# TASHIMASU_MAINBOARD_2020-07-29_17-58-20.net
KiCad netlist of a schematic drawn in EasyEDA
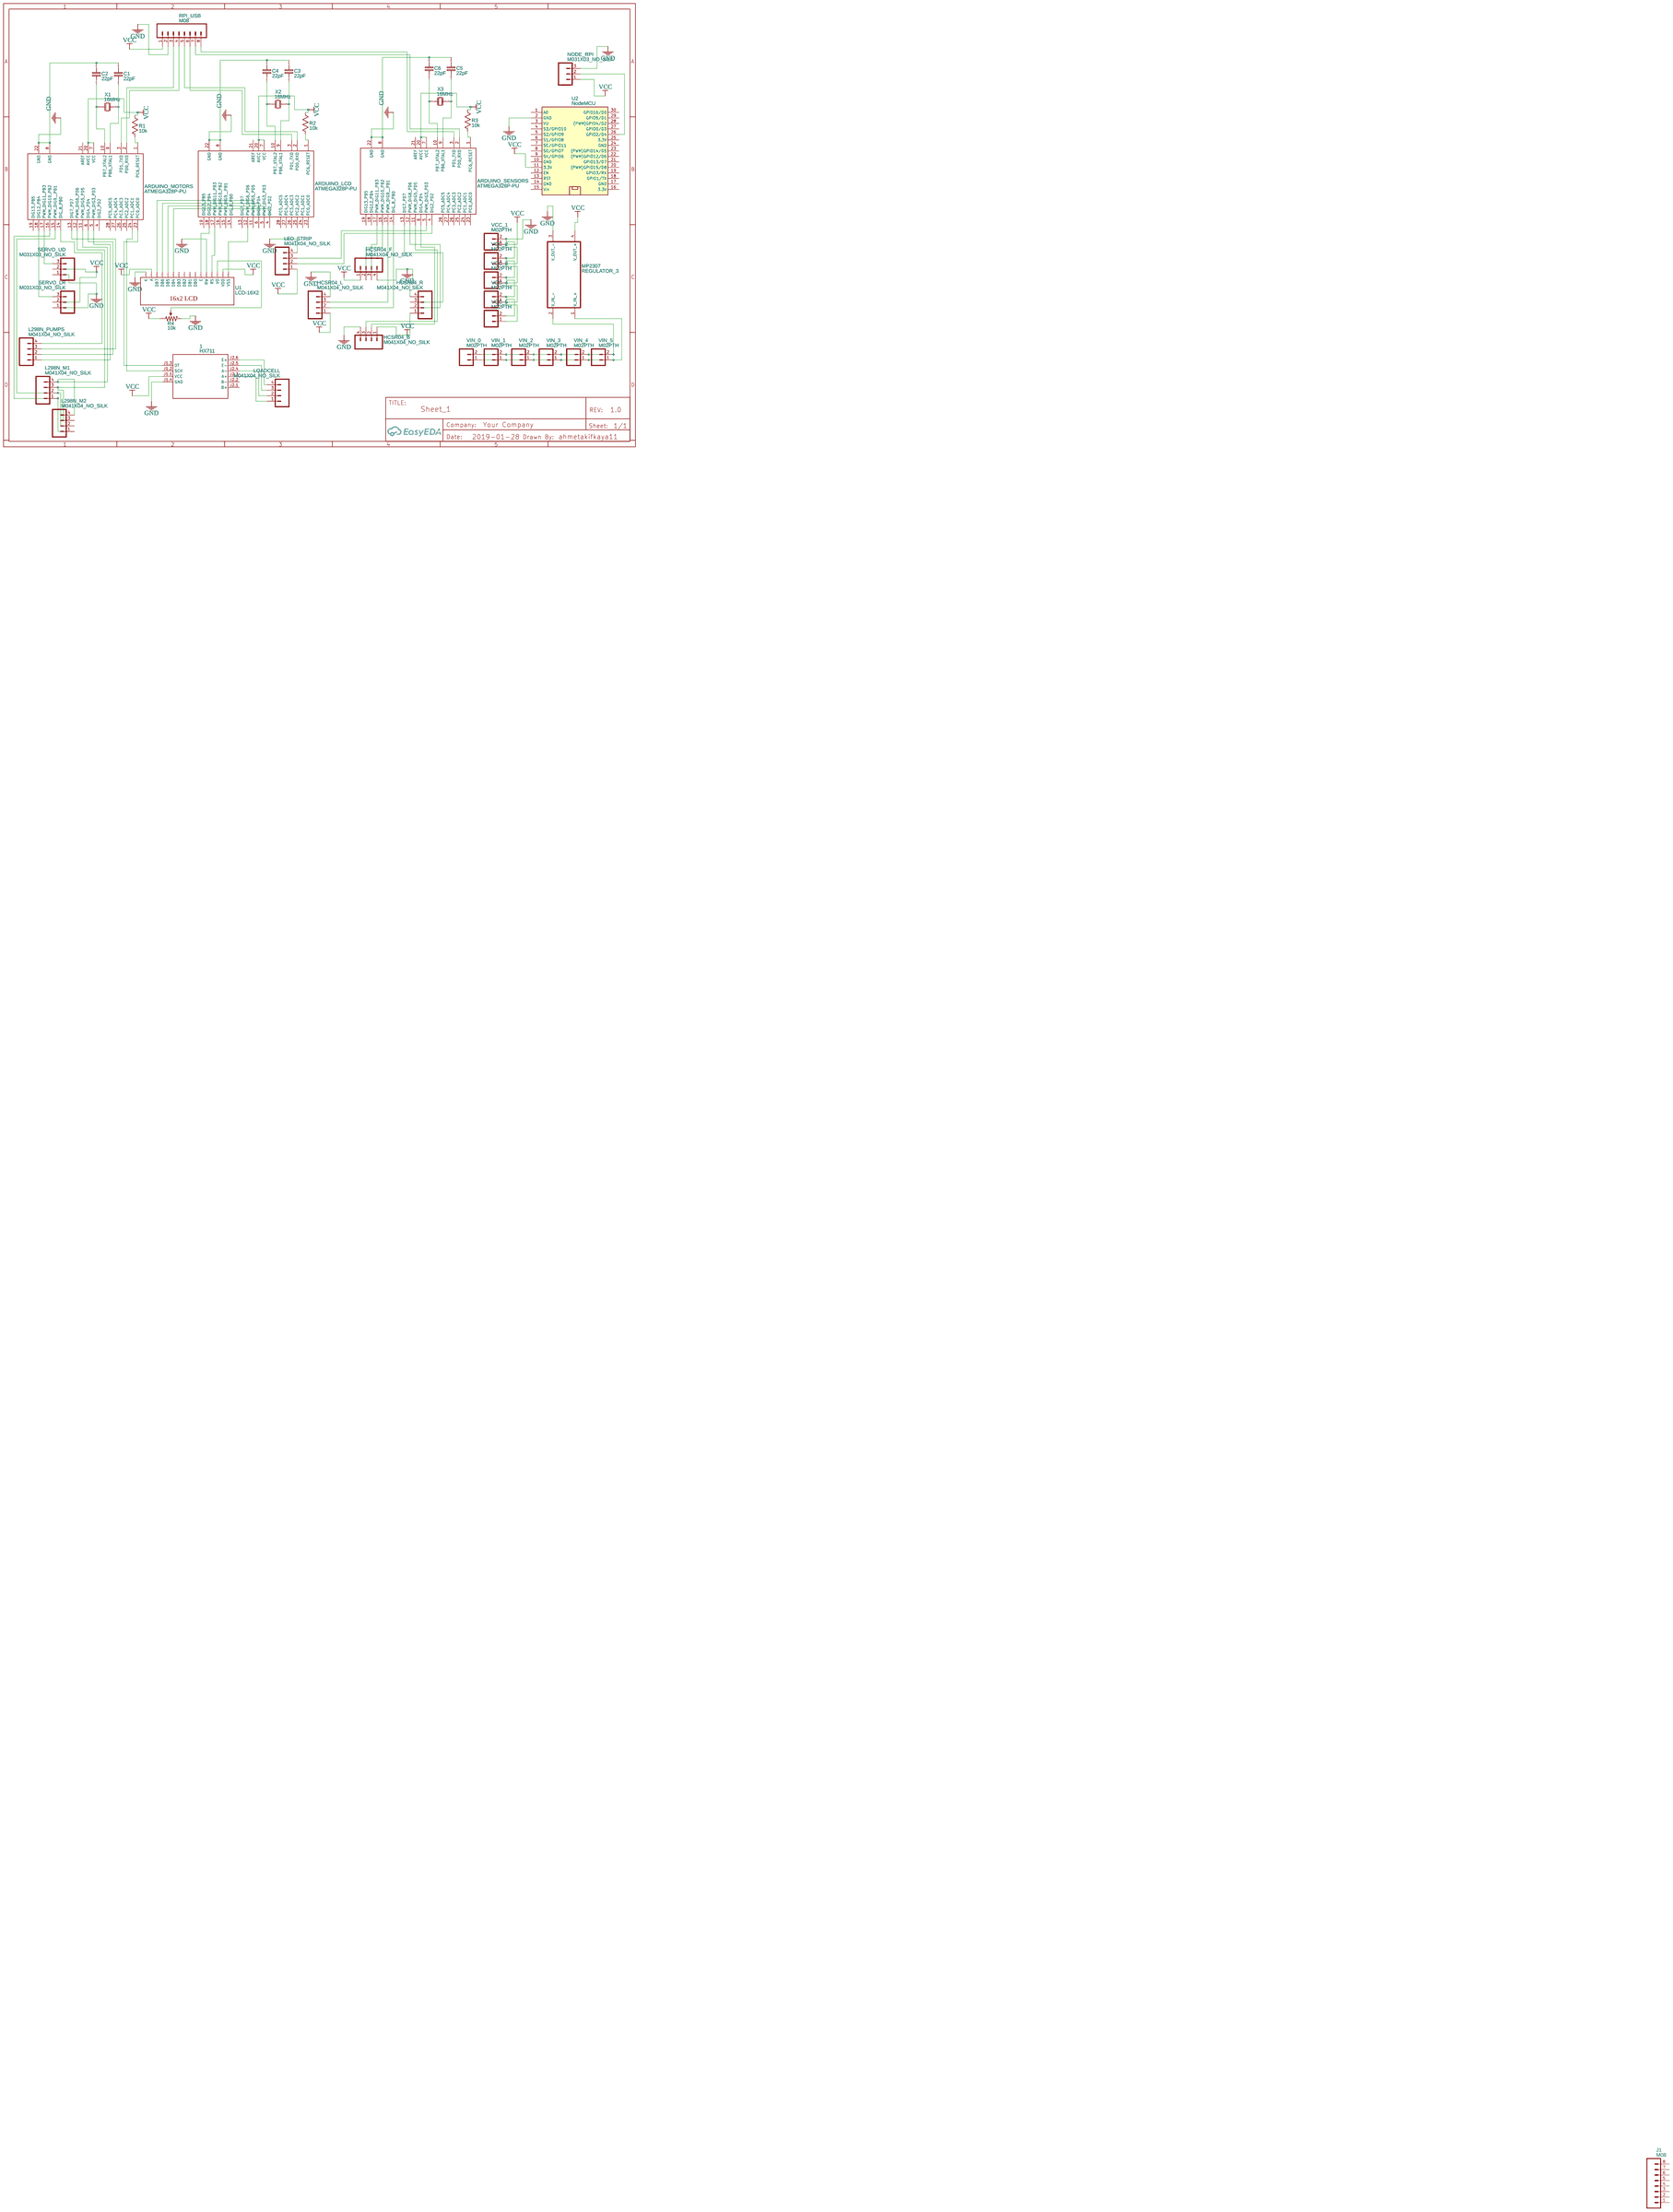
[diagram p0: schematic sheet]

(export (version "E")
  (design (tool "Eeschema 10.0.6"))
  (components
    (comp (ref "1")
      (value "HX711")
      (fields (field (name "BOM_Manufacturer Part") "?"))
      (libsource (lib "") (part "Unknown_350_680"))
    )
    (comp (ref "ARDUINO_LCD")
      (value "ATMEGA328P-PU")
      (fields (field (name "BOM_Supplier Part") "C33901"))
      (libsource (lib "") (part "Unknown_450_330"))
    )
    (comp (ref "ARDUINO_MOTORS")
      (value "ATMEGA328P-PU")
      (fields (field (name "BOM_Supplier Part") "C33901"))
      (libsource (lib "") (part "Unknown_140_335"))
    )
    (comp (ref "ARDUINO_SENSORS")
      (value "ATMEGA328P-PU")
      (fields (field (name "BOM_Supplier Part") "C33901"))
      (libsource (lib "") (part "Unknown_745_325"))
    )
    (comp (ref "C1")
      (value "22pF")
      (fields (field (name "BOM_Manufacturer Part") "?"))
      (libsource (lib "") (part "Cap_RAD-0.1_EU_1"))
    )
    (comp (ref "C2")
      (value "22pF")
      (fields (field (name "BOM_Manufacturer Part") "?"))
      (libsource (lib "") (part "Cap_RAD-0.1_EU_1"))
    )
    (comp (ref "C3")
      (value "22pF")
      (fields (field (name "BOM_Manufacturer Part") "?"))
      (libsource (lib "") (part "Cap_RAD-0.1_EU"))
    )
    (comp (ref "C4")
      (value "22pF")
      (fields (field (name "BOM_Manufacturer Part") "?"))
      (libsource (lib "") (part "Cap_RAD-0.1_EU_2"))
    )
    (comp (ref "C5")
      (value "22pF")
      (fields (field (name "BOM_Manufacturer Part") "?"))
      (libsource (lib "") (part "Cap_RAD-0.1_EU"))
    )
    (comp (ref "C6")
      (value "22pF")
      (fields (field (name "BOM_Manufacturer Part") "?"))
      (libsource (lib "") (part "Cap_RAD-0.1_EU"))
    )
    (comp (ref "HCSR04_B")
      (value "M041X04_NO_SILK")
      (fields (field (name "BOM_Manufacturer Part") "?"))
      (libsource (lib "") (part "Unknown_660_610"))
    )
    (comp (ref "HCSR04_F")
      (value "M041X04_NO_SILK")
      (fields (field (name "BOM_Manufacturer Part") "?"))
      (libsource (lib "") (part "Unknown_650_485"))
    )
    (comp (ref "HCSR04_L")
      (value "M041X04_NO_SILK")
      (fields (field (name "BOM_Manufacturer Part") "?"))
      (libsource (lib "") (part "Unknown_565_555"))
    )
    (comp (ref "HCSR04_R")
      (value "M041X04_NO_SILK")
      (fields (field (name "BOM_Manufacturer Part") "?"))
      (libsource (lib "") (part "Unknown_750_555"))
    )
    (comp (ref "J1")
      (value "M08")
      (fields (field (name "BOM_Manufacturer Part") "?"))
      (libsource (lib "") (part "Unknown_3000_4000"))
    )
    (comp (ref "L298N_M1")
      (value "M041X04_NO_SILK")
      (fields (field (name "BOM_Manufacturer Part") "?"))
      (libsource (lib "") (part "Unknown_70_710"))
    )
    (comp (ref "L298N_M2")
      (value "M041X04_NO_SILK")
      (fields (field (name "BOM_Manufacturer Part") "?"))
      (libsource (lib "") (part "Unknown_100_770"))
    )
    (comp (ref "L298N_PUMPS")
      (value "M041X04_NO_SILK")
      (fields (field (name "BOM_Manufacturer Part") "?"))
      (libsource (lib "") (part "Unknown_40_640"))
    )
    (comp (ref "LED_STRIP")
      (value "M041X04_NO_SILK")
      (fields (field (name "BOM_Manufacturer Part") "?"))
      (libsource (lib "") (part "Unknown_505_475"))
    )
    (comp (ref "LOADCELL")
      (value "M041X04_NO_SILK")
      (fields (field (name "BOM_Manufacturer Part") "?"))
      (libsource (lib "") (part "Unknown_490_715"))
    )
    (comp (ref "NODE_RPI")
      (value "M031X03_NO_SILK")
      (fields (field (name "BOM_Manufacturer Part") "?"))
      (libsource (lib "") (part "Unknown_1010_130"))
    )
    (comp (ref "R1")
      (value "10k")
      (fields (field (name "BOM_Manufacturer Part") "?"))
      (libsource (lib "") (part "Res_AXIAL-0.3(1/8W)_US"))
    )
    (comp (ref "R2")
      (value "10k")
      (fields (field (name "BOM_Manufacturer Part") "?"))
      (libsource (lib "") (part "Res_AXIAL-0.3(1/8W)_US"))
    )
    (comp (ref "R3")
      (value "10k")
      (fields (field (name "BOM_Manufacturer Part") "?"))
      (libsource (lib "") (part "Res_AXIAL-0.3(1/8W)_US"))
    )
    (comp (ref "R4")
      (value "10k")
      (fields
        (field (name "BOM_Manufacturer Part") "3386P-1-101LF")
        (field (name "BOM_Supplier Part") "C125022")
      )
      (libsource (lib "") (part "3386P-1-101LF_US"))
    )
    (comp (ref "REGULATOR_3")
      (value "MP2307")
      (fields (field (name "BOM_Manufacturer Part") "?"))
      (libsource (lib "") (part "Unknown_1010_565"))
    )
    (comp (ref "RPI_USB")
      (value "M08")
      (fields (field (name "BOM_Manufacturer Part") "?"))
      (libsource (lib "") (part "Unknown_280_60"))
    )
    (comp (ref "SERVO_LR")
      (value "M031X03_NO_SILK")
      (fields (field (name "BOM_Manufacturer Part") "?"))
      (libsource (lib "") (part "Unknown_110_545"))
    )
    (comp (ref "SERVO_UD")
      (value "M031X03_NO_SILK")
      (fields (field (name "BOM_Manufacturer Part") "?"))
      (libsource (lib "") (part "Unknown_110_485"))
    )
    (comp (ref "U1")
      (value "LCD-16X2")
      (fields (field (name "BOM_Manufacturer Part") "?"))
      (libsource (lib "") (part "Unknown_325_520"))
    )
    (comp (ref "U2")
      (value "NodeMCU")
      (fields (field (name "BOM_Manufacturer Part") "NodeMcu V3 LoLin"))
      (libsource (lib "") (part "Unknown_950_200"))
    )
    (comp (ref "VCC_1")
      (value "M02PTH")
      (fields (field (name "BOM_Manufacturer Part") "?"))
      (libsource (lib "") (part "Unknown_875_440"))
    )
    (comp (ref "VCC_2")
      (value "M02PTH")
      (fields (field (name "BOM_Manufacturer Part") "?"))
      (libsource (lib "") (part "Unknown_875_475"))
    )
    (comp (ref "VCC_3")
      (value "M02PTH")
      (fields (field (name "BOM_Manufacturer Part") "?"))
      (libsource (lib "") (part "Unknown_875_510"))
    )
    (comp (ref "VCC_4")
      (value "M02PTH")
      (fields (field (name "BOM_Manufacturer Part") "?"))
      (libsource (lib "") (part "Unknown_875_545"))
    )
    (comp (ref "VCC_5")
      (value "M02PTH")
      (fields (field (name "BOM_Manufacturer Part") "?"))
      (libsource (lib "") (part "Unknown_875_580"))
    )
    (comp (ref "VIN_0")
      (value "M02PTH")
      (fields (field (name "BOM_Manufacturer Part") "?"))
      (libsource (lib "") (part "Unknown_830_650"))
    )
    (comp (ref "VIN_1")
      (value "M02PTH")
      (fields (field (name "BOM_Manufacturer Part") "?"))
      (libsource (lib "") (part "Unknown_875_650"))
    )
    (comp (ref "VIN_2")
      (value "M02PTH")
      (fields (field (name "BOM_Manufacturer Part") "?"))
      (libsource (lib "") (part "Unknown_925_650"))
    )
    (comp (ref "VIN_3")
      (value "M02PTH")
      (fields (field (name "BOM_Manufacturer Part") "?"))
      (libsource (lib "") (part "Unknown_975_650"))
    )
    (comp (ref "VIN_4")
      (value "M02PTH")
      (fields (field (name "BOM_Manufacturer Part") "?"))
      (libsource (lib "") (part "Unknown_1025_650"))
    )
    (comp (ref "VIN_5")
      (value "M02PTH")
      (fields (field (name "BOM_Manufacturer Part") "?"))
      (libsource (lib "") (part "Unknown_1070_650"))
    )
    (comp (ref "X1")
      (value "16MHz")
      (fields
        (field (name "BOM_Manufacturer Part") "X49SD12MSD2SC")
        (field (name "BOM_Supplier Part") "C16369")
      )
      (libsource (lib "") (part "X49SD12MSD2SC"))
    )
    (comp (ref "X2")
      (value "16MHz")
      (fields
        (field (name "BOM_Manufacturer Part") "X49SD12MSD2SC")
        (field (name "BOM_Supplier Part") "C16369")
      )
      (libsource (lib "") (part "X49SD12MSD2SC"))
    )
    (comp (ref "X3")
      (value "16MHz")
      (fields
        (field (name "BOM_Manufacturer Part") "X49SD12MSD2SC")
        (field (name "BOM_Supplier Part") "C16369")
      )
      (libsource (lib "") (part "X49SD12MSD2SC"))
    )
  )
  (nets
    (net (code "1") (name "GND") (class "Default")
      (node (ref "1") (pin "J1.4") (pinfunction "GND_J1.4") (pintype "bidirectional"))
      (node (ref "ARDUINO_LCD") (pin "22") (pinfunction "GND_22") (pintype "passive"))
      (node (ref "ARDUINO_LCD") (pin "8") (pinfunction "GND_8") (pintype "passive"))
      (node (ref "ARDUINO_MOTORS") (pin "22") (pinfunction "GND_22") (pintype "passive"))
      (node (ref "ARDUINO_MOTORS") (pin "8") (pinfunction "GND_8") (pintype "passive"))
      (node (ref "ARDUINO_SENSORS") (pin "22") (pinfunction "GND_22") (pintype "passive"))
      (node (ref "ARDUINO_SENSORS") (pin "8") (pinfunction "GND_8") (pintype "passive"))
      (node (ref "C1") (pin "2") (pinfunction "2_2") (pintype "unspecified"))
      (node (ref "C2") (pin "2") (pinfunction "2_2") (pintype "unspecified"))
      (node (ref "C3") (pin "2") (pinfunction "2_2") (pintype "unspecified"))
      (node (ref "C4") (pin "2") (pinfunction "2_2") (pintype "unspecified"))
      (node (ref "C5") (pin "2") (pinfunction "2_2") (pintype "unspecified"))
      (node (ref "C6") (pin "2") (pinfunction "2_2") (pintype "unspecified"))
      (node (ref "HCSR04_B") (pin "4") (pinfunction "4_4") (pintype "unspecified"))
      (node (ref "HCSR04_F") (pin "4") (pinfunction "4_4") (pintype "unspecified"))
      (node (ref "HCSR04_L") (pin "4") (pinfunction "4_4") (pintype "unspecified"))
      (node (ref "HCSR04_R") (pin "4") (pinfunction "4_4") (pintype "unspecified"))
      (node (ref "LED_STRIP") (pin "4") (pinfunction "4_4") (pintype "unspecified"))
      (node (ref "NODE_RPI") (pin "3") (pinfunction "3_3") (pintype "unspecified"))
      (node (ref "R4") (pin "1") (pinfunction "1_1") (pintype "unspecified"))
      (node (ref "REGULATOR_3") (pin "3") (pinfunction "V_OUT_-_3") (pintype "unspecified"))
      (node (ref "RPI_USB") (pin "2") (pinfunction "2_2") (pintype "bidirectional"))
      (node (ref "SERVO_LR") (pin "1") (pinfunction "1_1") (pintype "unspecified"))
      (node (ref "SERVO_UD") (pin "1") (pinfunction "1_1") (pintype "unspecified"))
      (node (ref "U1") (pin "16") (pinfunction "K_16") (pintype "passive"))
      (node (ref "U1") (pin "5") (pinfunction "RW_5") (pintype "input"))
      (node (ref "U2") (pin "2") (pinfunction "GND_2") (pintype "unspecified"))
      (node (ref "VCC_1") (pin "2") (pinfunction "2_2") (pintype "unspecified"))
      (node (ref "VCC_2") (pin "2") (pinfunction "2_2") (pintype "unspecified"))
      (node (ref "VCC_3") (pin "2") (pinfunction "2_2") (pintype "unspecified"))
      (node (ref "VCC_4") (pin "2") (pinfunction "2_2") (pintype "unspecified"))
      (node (ref "VCC_5") (pin "2") (pinfunction "2_2") (pintype "unspecified"))
    )
    (net (code "2") (name "Net-(1-A+)") (class "Default")
      (node (ref "1") (pin "J2.3") (pinfunction "A+_J2.3") (pintype "bidirectional"))
      (node (ref "LOADCELL") (pin "1") (pinfunction "1_1") (pintype "unspecified"))
    )
    (net (code "3") (name "Net-(1-A-)") (class "Default")
      (node (ref "1") (pin "J2.4") (pinfunction "A-_J2.4") (pintype "bidirectional"))
      (node (ref "LOADCELL") (pin "2") (pinfunction "2_2") (pintype "unspecified"))
    )
    (net (code "4") (name "Net-(1-DT)") (class "Default")
      (node (ref "1") (pin "J1.3") (pinfunction "DT_J1.3") (pintype "bidirectional"))
      (node (ref "ARDUINO_MOTORS") (pin "23") (pinfunction "PC0_ADC0_23") (pintype "bidirectional"))
    )
    (net (code "5") (name "Net-(1-E+)") (class "Default")
      (node (ref "1") (pin "J2.6") (pinfunction "E+_J2.6") (pintype "bidirectional"))
      (node (ref "LOADCELL") (pin "4") (pinfunction "4_4") (pintype "unspecified"))
    )
    (net (code "6") (name "Net-(1-E-)") (class "Default")
      (node (ref "1") (pin "J2.5") (pinfunction "E-_J2.5") (pintype "bidirectional"))
      (node (ref "LOADCELL") (pin "3") (pinfunction "3_3") (pintype "unspecified"))
    )
    (net (code "7") (name "Net-(1-SCK)") (class "Default")
      (node (ref "1") (pin "J1.2") (pinfunction "SCK_J1.2") (pintype "bidirectional"))
      (node (ref "ARDUINO_MOTORS") (pin "24") (pinfunction "PC1_ADC1_24") (pintype "bidirectional"))
    )
    (net (code "8") (name "Net-(ARDUINO_LCD-DIG2_PD2)") (class "Default")
      (node (ref "ARDUINO_LCD") (pin "4") (pinfunction "DIG2_PD2_4") (pintype "bidirectional"))
      (node (ref "U1") (pin "11") (pinfunction "DB4_11") (pintype "unspecified"))
    )
    (net (code "9") (name "Net-(ARDUINO_LCD-DIG4_PD4)") (class "Default")
      (node (ref "ARDUINO_LCD") (pin "6") (pinfunction "DIG4_PD4_6") (pintype "bidirectional"))
      (node (ref "U1") (pin "13") (pinfunction "DB6_13") (pintype "unspecified"))
    )
    (net (code "10") (name "Net-(ARDUINO_LCD-DIG12_PB4)") (class "Default")
      (node (ref "ARDUINO_LCD") (pin "18") (pinfunction "DIG12_PB4_18") (pintype "bidirectional"))
      (node (ref "U1") (pin "6") (pinfunction "E_6") (pintype "input"))
    )
    (net (code "11") (name "Net-(ARDUINO_LCD-PB6_XTAL1)") (class "Default")
      (node (ref "ARDUINO_LCD") (pin "9") (pinfunction "PB6_XTAL1_9") (pintype "bidirectional"))
      (node (ref "C3") (pin "1") (pinfunction "1_1") (pintype "unspecified"))
      (node (ref "X2") (pin "2") (pinfunction "OSC2_2") (pintype "input"))
    )
    (net (code "12") (name "Net-(ARDUINO_LCD-PB7_XTAL2)") (class "Default")
      (node (ref "ARDUINO_LCD") (pin "10") (pinfunction "PB7_XTAL2_10") (pintype "bidirectional"))
      (node (ref "C4") (pin "1") (pinfunction "1_1") (pintype "unspecified"))
      (node (ref "X2") (pin "1") (pinfunction "OSC1_1") (pintype "input"))
    )
    (net (code "13") (name "Net-(ARDUINO_LCD-PC6_RESET)") (class "Default")
      (node (ref "ARDUINO_LCD") (pin "1") (pinfunction "PC6_RESET_1") (pintype "bidirectional"))
      (node (ref "R2") (pin "2") (pinfunction "2_2") (pintype "unspecified"))
    )
    (net (code "14") (name "Net-(ARDUINO_LCD-PD0_RXD)") (class "Default")
      (node (ref "ARDUINO_LCD") (pin "2") (pinfunction "PD0_RXD_2") (pintype "bidirectional"))
      (node (ref "RPI_USB") (pin "5") (pinfunction "5_5") (pintype "bidirectional"))
    )
    (net (code "15") (name "Net-(ARDUINO_LCD-PD1_TXD)") (class "Default")
      (node (ref "ARDUINO_LCD") (pin "3") (pinfunction "PD1_TXD_3") (pintype "bidirectional"))
      (node (ref "RPI_USB") (pin "6") (pinfunction "6_6") (pintype "bidirectional"))
    )
    (net (code "16") (name "Net-(ARDUINO_LCD-PWM_DIG3_PD3)") (class "Default")
      (node (ref "ARDUINO_LCD") (pin "5") (pinfunction "PWM_DIG3_PD3_5") (pintype "bidirectional"))
      (node (ref "U1") (pin "12") (pinfunction "DB5_12") (pintype "unspecified"))
    )
    (net (code "17") (name "Net-(ARDUINO_LCD-PWM_DIG5_PD5)") (class "Default")
      (node (ref "ARDUINO_LCD") (pin "11") (pinfunction "PWM_DIG5_PD5_11") (pintype "bidirectional"))
      (node (ref "U1") (pin "14") (pinfunction "DB7_14") (pintype "unspecified"))
    )
    (net (code "18") (name "Net-(ARDUINO_LCD-PWM_DIG6_PD6)") (class "Default")
      (node (ref "ARDUINO_LCD") (pin "12") (pinfunction "PWM_DIG6_PD6_12") (pintype "bidirectional"))
      (node (ref "U1") (pin "1") (pinfunction "VSS_1") (pintype "passive"))
    )
    (net (code "19") (name "Net-(ARDUINO_LCD-PWM_DIG11_PB3)") (class "Default")
      (node (ref "ARDUINO_LCD") (pin "17") (pinfunction "PWM_DIG11_PB3_17") (pintype "bidirectional"))
      (node (ref "U1") (pin "4") (pinfunction "RS_4") (pintype "input"))
    )
    (net (code "20") (name "Net-(ARDUINO_MOTORS-DIG4_PD4)") (class "Default")
      (node (ref "ARDUINO_MOTORS") (pin "6") (pinfunction "DIG4_PD4_6") (pintype "bidirectional"))
      (node (ref "L298N_PUMPS") (pin "2") (pinfunction "2_2") (pintype "unspecified"))
    )
    (net (code "21") (name "Net-(ARDUINO_MOTORS-DIG7_PD7)") (class "Default")
      (node (ref "ARDUINO_MOTORS") (pin "13") (pinfunction "DIG7_PD7_13") (pintype "bidirectional"))
      (node (ref "L298N_PUMPS") (pin "3") (pinfunction "3_3") (pintype "unspecified"))
    )
    (net (code "22") (name "Net-(ARDUINO_MOTORS-DIG12_PB4)") (class "Default")
      (node (ref "ARDUINO_MOTORS") (pin "18") (pinfunction "DIG12_PB4_18") (pintype "bidirectional"))
      (node (ref "SERVO_LR") (pin "3") (pinfunction "3_3") (pintype "unspecified"))
    )
    (net (code "23") (name "Net-(ARDUINO_MOTORS-DIG_8_PB0)") (class "Default")
      (node (ref "ARDUINO_MOTORS") (pin "14") (pinfunction "DIG_8_PB0_14") (pintype "bidirectional"))
      (node (ref "L298N_PUMPS") (pin "4") (pinfunction "4_4") (pintype "unspecified"))
    )
    (net (code "24") (name "Net-(ARDUINO_MOTORS-PB6_XTAL1)") (class "Default")
      (node (ref "ARDUINO_MOTORS") (pin "9") (pinfunction "PB6_XTAL1_9") (pintype "bidirectional"))
      (node (ref "C1") (pin "1") (pinfunction "1_1") (pintype "unspecified"))
      (node (ref "X1") (pin "2") (pinfunction "OSC2_2") (pintype "input"))
    )
    (net (code "25") (name "Net-(ARDUINO_MOTORS-PB7_XTAL2)") (class "Default")
      (node (ref "ARDUINO_MOTORS") (pin "10") (pinfunction "PB7_XTAL2_10") (pintype "bidirectional"))
      (node (ref "C2") (pin "1") (pinfunction "1_1") (pintype "unspecified"))
      (node (ref "X1") (pin "1") (pinfunction "OSC1_1") (pintype "input"))
    )
    (net (code "26") (name "Net-(ARDUINO_MOTORS-PC6_RESET)") (class "Default")
      (node (ref "ARDUINO_MOTORS") (pin "1") (pinfunction "PC6_RESET_1") (pintype "bidirectional"))
      (node (ref "R1") (pin "2") (pinfunction "2_2") (pintype "unspecified"))
    )
    (net (code "27") (name "Net-(ARDUINO_MOTORS-PD0_RXD)") (class "Default")
      (node (ref "ARDUINO_MOTORS") (pin "2") (pinfunction "PD0_RXD_2") (pintype "bidirectional"))
      (node (ref "RPI_USB") (pin "3") (pinfunction "3_3") (pintype "bidirectional"))
    )
    (net (code "28") (name "Net-(ARDUINO_MOTORS-PD1_TXD)") (class "Default")
      (node (ref "ARDUINO_MOTORS") (pin "3") (pinfunction "PD1_TXD_3") (pintype "bidirectional"))
      (node (ref "RPI_USB") (pin "4") (pinfunction "4_4") (pintype "bidirectional"))
    )
    (net (code "29") (name "Net-(ARDUINO_MOTORS-PWM_DIG3_PD3)") (class "Default")
      (node (ref "ARDUINO_MOTORS") (pin "5") (pinfunction "PWM_DIG3_PD3_5") (pintype "bidirectional"))
      (node (ref "L298N_PUMPS") (pin "1") (pinfunction "1_1") (pintype "unspecified"))
    )
    (net (code "30") (name "Net-(ARDUINO_MOTORS-PWM_DIG5_PD5)") (class "Default")
      (node (ref "ARDUINO_MOTORS") (pin "11") (pinfunction "PWM_DIG5_PD5_11") (pintype "bidirectional"))
      (node (ref "L298N_M1") (pin "4") (pinfunction "4_4") (pintype "unspecified"))
      (node (ref "L298N_M2") (pin "4") (pinfunction "4_4") (pintype "unspecified"))
    )
    (net (code "31") (name "Net-(ARDUINO_MOTORS-PWM_DIG6_PD6)") (class "Default")
      (node (ref "ARDUINO_MOTORS") (pin "12") (pinfunction "PWM_DIG6_PD6_12") (pintype "bidirectional"))
      (node (ref "L298N_M1") (pin "3") (pinfunction "3_3") (pintype "unspecified"))
      (node (ref "L298N_M2") (pin "3") (pinfunction "3_3") (pintype "unspecified"))
    )
    (net (code "32") (name "Net-(ARDUINO_MOTORS-PWM_DIG9__PB1)") (class "Default")
      (node (ref "ARDUINO_MOTORS") (pin "15") (pinfunction "PWM_DIG9__PB1_15") (pintype "bidirectional"))
      (node (ref "L298N_M1") (pin "2") (pinfunction "2_2") (pintype "unspecified"))
      (node (ref "L298N_M2") (pin "2") (pinfunction "2_2") (pintype "unspecified"))
    )
    (net (code "33") (name "Net-(ARDUINO_MOTORS-PWM_DIG10_PB2)") (class "Default")
      (node (ref "ARDUINO_MOTORS") (pin "16") (pinfunction "PWM_DIG10_PB2_16") (pintype "bidirectional"))
      (node (ref "L298N_M1") (pin "1") (pinfunction "1_1") (pintype "unspecified"))
      (node (ref "L298N_M2") (pin "1") (pinfunction "1_1") (pintype "unspecified"))
    )
    (net (code "34") (name "Net-(ARDUINO_MOTORS-PWM_DIG11_PB3)") (class "Default")
      (node (ref "ARDUINO_MOTORS") (pin "17") (pinfunction "PWM_DIG11_PB3_17") (pintype "bidirectional"))
      (node (ref "SERVO_UD") (pin "3") (pinfunction "3_3") (pintype "unspecified"))
    )
    (net (code "35") (name "Net-(ARDUINO_SENSORS-DIG2_PD2)") (class "Default")
      (node (ref "ARDUINO_SENSORS") (pin "4") (pinfunction "DIG2_PD2_4") (pintype "bidirectional"))
      (node (ref "LED_STRIP") (pin "2") (pinfunction "2_2") (pintype "unspecified"))
    )
    (net (code "36") (name "Net-(ARDUINO_SENSORS-DIG4_PD4)") (class "Default")
      (node (ref "ARDUINO_SENSORS") (pin "6") (pinfunction "DIG4_PD4_6") (pintype "bidirectional"))
      (node (ref "HCSR04_B") (pin "2") (pinfunction "2_2") (pintype "unspecified"))
    )
    (net (code "37") (name "Net-(ARDUINO_SENSORS-DIG7_PD7)") (class "Default")
      (node (ref "ARDUINO_SENSORS") (pin "13") (pinfunction "DIG7_PD7_13") (pintype "bidirectional"))
      (node (ref "HCSR04_R") (pin "3") (pinfunction "3_3") (pintype "unspecified"))
    )
    (net (code "38") (name "Net-(ARDUINO_SENSORS-DIG_8_PB0)") (class "Default")
      (node (ref "ARDUINO_SENSORS") (pin "14") (pinfunction "DIG_8_PB0_14") (pintype "bidirectional"))
      (node (ref "HCSR04_L") (pin "2") (pinfunction "2_2") (pintype "unspecified"))
    )
    (net (code "39") (name "Net-(ARDUINO_SENSORS-PB6_XTAL1)") (class "Default")
      (node (ref "ARDUINO_SENSORS") (pin "9") (pinfunction "PB6_XTAL1_9") (pintype "bidirectional"))
      (node (ref "C5") (pin "1") (pinfunction "1_1") (pintype "unspecified"))
      (node (ref "X3") (pin "2") (pinfunction "OSC2_2") (pintype "input"))
    )
    (net (code "40") (name "Net-(ARDUINO_SENSORS-PB7_XTAL2)") (class "Default")
      (node (ref "ARDUINO_SENSORS") (pin "10") (pinfunction "PB7_XTAL2_10") (pintype "bidirectional"))
      (node (ref "C6") (pin "1") (pinfunction "1_1") (pintype "unspecified"))
      (node (ref "X3") (pin "1") (pinfunction "OSC1_1") (pintype "input"))
    )
    (net (code "41") (name "Net-(ARDUINO_SENSORS-PC6_RESET)") (class "Default")
      (node (ref "ARDUINO_SENSORS") (pin "1") (pinfunction "PC6_RESET_1") (pintype "bidirectional"))
      (node (ref "R3") (pin "2") (pinfunction "2_2") (pintype "unspecified"))
    )
    (net (code "42") (name "Net-(ARDUINO_SENSORS-PD0_RXD)") (class "Default")
      (node (ref "ARDUINO_SENSORS") (pin "2") (pinfunction "PD0_RXD_2") (pintype "bidirectional"))
      (node (ref "RPI_USB") (pin "7") (pinfunction "7_7") (pintype "bidirectional"))
    )
    (net (code "43") (name "Net-(ARDUINO_SENSORS-PD1_TXD)") (class "Default")
      (node (ref "ARDUINO_SENSORS") (pin "3") (pinfunction "PD1_TXD_3") (pintype "bidirectional"))
      (node (ref "RPI_USB") (pin "8") (pinfunction "8_8") (pintype "bidirectional"))
    )
    (net (code "44") (name "Net-(ARDUINO_SENSORS-PWM_DIG3_PD3)") (class "Default")
      (node (ref "ARDUINO_SENSORS") (pin "5") (pinfunction "PWM_DIG3_PD3_5") (pintype "bidirectional"))
      (node (ref "LED_STRIP") (pin "3") (pinfunction "3_3") (pintype "unspecified"))
    )
    (net (code "45") (name "Net-(ARDUINO_SENSORS-PWM_DIG5_PD5)") (class "Default")
      (node (ref "ARDUINO_SENSORS") (pin "11") (pinfunction "PWM_DIG5_PD5_11") (pintype "bidirectional"))
      (node (ref "HCSR04_B") (pin "3") (pinfunction "3_3") (pintype "unspecified"))
    )
    (net (code "46") (name "Net-(ARDUINO_SENSORS-PWM_DIG6_PD6)") (class "Default")
      (node (ref "ARDUINO_SENSORS") (pin "12") (pinfunction "PWM_DIG6_PD6_12") (pintype "bidirectional"))
      (node (ref "HCSR04_R") (pin "2") (pinfunction "2_2") (pintype "unspecified"))
    )
    (net (code "47") (name "Net-(ARDUINO_SENSORS-PWM_DIG9__PB1)") (class "Default")
      (node (ref "ARDUINO_SENSORS") (pin "15") (pinfunction "PWM_DIG9__PB1_15") (pintype "bidirectional"))
      (node (ref "HCSR04_L") (pin "3") (pinfunction "3_3") (pintype "unspecified"))
    )
    (net (code "48") (name "Net-(ARDUINO_SENSORS-PWM_DIG10_PB2)") (class "Default")
      (node (ref "ARDUINO_SENSORS") (pin "16") (pinfunction "PWM_DIG10_PB2_16") (pintype "bidirectional"))
      (node (ref "HCSR04_F") (pin "2") (pinfunction "2_2") (pintype "unspecified"))
    )
    (net (code "49") (name "Net-(ARDUINO_SENSORS-PWM_DIG11_PB3)") (class "Default")
      (node (ref "ARDUINO_SENSORS") (pin "17") (pinfunction "PWM_DIG11_PB3_17") (pintype "bidirectional"))
      (node (ref "HCSR04_F") (pin "3") (pinfunction "3_3") (pintype "unspecified"))
    )
    (net (code "50") (name "Net-(REGULATOR_3-V_IN_+)") (class "Default")
      (node (ref "REGULATOR_3") (pin "1") (pinfunction "V_IN_+_1") (pintype "unspecified"))
      (node (ref "VIN_0") (pin "1") (pinfunction "1_1") (pintype "unspecified"))
      (node (ref "VIN_1") (pin "1") (pinfunction "1_1") (pintype "unspecified"))
      (node (ref "VIN_2") (pin "1") (pinfunction "1_1") (pintype "unspecified"))
      (node (ref "VIN_3") (pin "1") (pinfunction "1_1") (pintype "unspecified"))
      (node (ref "VIN_4") (pin "1") (pinfunction "1_1") (pintype "unspecified"))
      (node (ref "VIN_5") (pin "1") (pinfunction "1_1") (pintype "unspecified"))
    )
    (net (code "51") (name "Net-(REGULATOR_3-V_IN_-)") (class "Default")
      (node (ref "REGULATOR_3") (pin "2") (pinfunction "V_IN_-_2") (pintype "unspecified"))
      (node (ref "VIN_0") (pin "2") (pinfunction "2_2") (pintype "unspecified"))
      (node (ref "VIN_1") (pin "2") (pinfunction "2_2") (pintype "unspecified"))
      (node (ref "VIN_2") (pin "2") (pinfunction "2_2") (pintype "unspecified"))
      (node (ref "VIN_3") (pin "2") (pinfunction "2_2") (pintype "unspecified"))
      (node (ref "VIN_4") (pin "2") (pinfunction "2_2") (pintype "unspecified"))
      (node (ref "VIN_5") (pin "2") (pinfunction "2_2") (pintype "unspecified"))
    )
    (net (code "52") (name "Net-(U1-VO)") (class "Default")
      (node (ref "R4") (pin "2") (pinfunction "2_2") (pintype "unspecified"))
      (node (ref "U1") (pin "3") (pinfunction "VO_3") (pintype "unspecified"))
    )
    (net (code "53") (name "Net-(U2-GPIO2{slash}D4)") (class "Default")
      (node (ref "NODE_RPI") (pin "2") (pinfunction "2_2") (pintype "unspecified"))
      (node (ref "U2") (pin "26") (pinfunction "GPIO2/D4_26") (pintype "unspecified"))
    )
    (net (code "54") (name "VCC") (class "Default")
      (node (ref "1") (pin "J1.1") (pinfunction "VCC_J1.1") (pintype "bidirectional"))
      (node (ref "ARDUINO_LCD") (pin "20") (pinfunction "AVCC_20") (pintype "passive"))
      (node (ref "ARDUINO_LCD") (pin "7") (pinfunction "VCC_7") (pintype "passive"))
      (node (ref "ARDUINO_MOTORS") (pin "20") (pinfunction "AVCC_20") (pintype "passive"))
      (node (ref "ARDUINO_MOTORS") (pin "7") (pinfunction "VCC_7") (pintype "passive"))
      (node (ref "ARDUINO_SENSORS") (pin "20") (pinfunction "AVCC_20") (pintype "passive"))
      (node (ref "ARDUINO_SENSORS") (pin "7") (pinfunction "VCC_7") (pintype "passive"))
      (node (ref "HCSR04_B") (pin "1") (pinfunction "1_1") (pintype "unspecified"))
      (node (ref "HCSR04_F") (pin "1") (pinfunction "1_1") (pintype "unspecified"))
      (node (ref "HCSR04_L") (pin "1") (pinfunction "1_1") (pintype "unspecified"))
      (node (ref "HCSR04_R") (pin "1") (pinfunction "1_1") (pintype "unspecified"))
      (node (ref "LED_STRIP") (pin "1") (pinfunction "1_1") (pintype "unspecified"))
      (node (ref "NODE_RPI") (pin "1") (pinfunction "1_1") (pintype "unspecified"))
      (node (ref "R1") (pin "1") (pinfunction "1_1") (pintype "unspecified"))
      (node (ref "R2") (pin "1") (pinfunction "1_1") (pintype "unspecified"))
      (node (ref "R3") (pin "1") (pinfunction "1_1") (pintype "unspecified"))
      (node (ref "R4") (pin "3") (pinfunction "3_3") (pintype "unspecified"))
      (node (ref "REGULATOR_3") (pin "4") (pinfunction "V_OUT_+_4") (pintype "unspecified"))
      (node (ref "RPI_USB") (pin "1") (pinfunction "1_1") (pintype "bidirectional"))
      (node (ref "SERVO_LR") (pin "2") (pinfunction "2_2") (pintype "unspecified"))
      (node (ref "SERVO_UD") (pin "2") (pinfunction "2_2") (pintype "unspecified"))
      (node (ref "U1") (pin "15") (pinfunction "A_15") (pintype "passive"))
      (node (ref "U1") (pin "2") (pinfunction "VDD_2") (pintype "passive"))
      (node (ref "U2") (pin "11") (pinfunction "3.3V_11") (pintype "unspecified"))
      (node (ref "VCC_1") (pin "1") (pinfunction "1_1") (pintype "unspecified"))
      (node (ref "VCC_2") (pin "1") (pinfunction "1_1") (pintype "unspecified"))
      (node (ref "VCC_3") (pin "1") (pinfunction "1_1") (pintype "unspecified"))
      (node (ref "VCC_4") (pin "1") (pinfunction "1_1") (pintype "unspecified"))
      (node (ref "VCC_5") (pin "1") (pinfunction "1_1") (pintype "unspecified"))
    )
    (net (code "55") (name "unconnected-(1-B+-PadJ2.1)") (class "Default")
      (node (ref "1") (pin "J2.1") (pinfunction "B+_J2.1") (pintype "bidirectional"))
    )
    (net (code "56") (name "unconnected-(1-B--PadJ2.2)") (class "Default")
      (node (ref "1") (pin "J2.2") (pinfunction "B-_J2.2") (pintype "bidirectional"))
    )
    (net (code "57") (name "unconnected-(ARDUINO_LCD-AREF-Pad21)") (class "Default")
      (node (ref "ARDUINO_LCD") (pin "21") (pinfunction "AREF_21") (pintype "passive"))
    )
    (net (code "58") (name "unconnected-(ARDUINO_LCD-DIG7_PD7-Pad13)") (class "Default")
      (node (ref "ARDUINO_LCD") (pin "13") (pinfunction "DIG7_PD7_13") (pintype "bidirectional"))
    )
    (net (code "59") (name "unconnected-(ARDUINO_LCD-DIG13_PB5-Pad19)") (class "Default")
      (node (ref "ARDUINO_LCD") (pin "19") (pinfunction "DIG13_PB5_19") (pintype "bidirectional"))
    )
    (net (code "60") (name "unconnected-(ARDUINO_LCD-DIG_8_PB0-Pad14)") (class "Default")
      (node (ref "ARDUINO_LCD") (pin "14") (pinfunction "DIG_8_PB0_14") (pintype "bidirectional"))
    )
    (net (code "61") (name "unconnected-(ARDUINO_LCD-PC0_ADC0-Pad23)") (class "Default")
      (node (ref "ARDUINO_LCD") (pin "23") (pinfunction "PC0_ADC0_23") (pintype "bidirectional"))
    )
    (net (code "62") (name "unconnected-(ARDUINO_LCD-PC1_ADC1-Pad24)") (class "Default")
      (node (ref "ARDUINO_LCD") (pin "24") (pinfunction "PC1_ADC1_24") (pintype "bidirectional"))
    )
    (net (code "63") (name "unconnected-(ARDUINO_LCD-PC2_ADC2-Pad25)") (class "Default")
      (node (ref "ARDUINO_LCD") (pin "25") (pinfunction "PC2_ADC2_25") (pintype "bidirectional"))
    )
    (net (code "64") (name "unconnected-(ARDUINO_LCD-PC3_ADC3-Pad26)") (class "Default")
      (node (ref "ARDUINO_LCD") (pin "26") (pinfunction "PC3_ADC3_26") (pintype "bidirectional"))
    )
    (net (code "65") (name "unconnected-(ARDUINO_LCD-PC4_ADC4-Pad27)") (class "Default")
      (node (ref "ARDUINO_LCD") (pin "27") (pinfunction "PC4_ADC4_27") (pintype "bidirectional"))
    )
    (net (code "66") (name "unconnected-(ARDUINO_LCD-PC5_ADC5-Pad28)") (class "Default")
      (node (ref "ARDUINO_LCD") (pin "28") (pinfunction "PC5_ADC5_28") (pintype "bidirectional"))
    )
    (net (code "67") (name "unconnected-(ARDUINO_LCD-PWM_DIG9__PB1-Pad15)") (class "Default")
      (node (ref "ARDUINO_LCD") (pin "15") (pinfunction "PWM_DIG9__PB1_15") (pintype "bidirectional"))
    )
    (net (code "68") (name "unconnected-(ARDUINO_LCD-PWM_DIG10_PB2-Pad16)") (class "Default")
      (node (ref "ARDUINO_LCD") (pin "16") (pinfunction "PWM_DIG10_PB2_16") (pintype "bidirectional"))
    )
    (net (code "69") (name "unconnected-(ARDUINO_MOTORS-AREF-Pad21)") (class "Default")
      (node (ref "ARDUINO_MOTORS") (pin "21") (pinfunction "AREF_21") (pintype "passive"))
    )
    (net (code "70") (name "unconnected-(ARDUINO_MOTORS-DIG2_PD2-Pad4)") (class "Default")
      (node (ref "ARDUINO_MOTORS") (pin "4") (pinfunction "DIG2_PD2_4") (pintype "bidirectional"))
    )
    (net (code "71") (name "unconnected-(ARDUINO_MOTORS-DIG13_PB5-Pad19)") (class "Default")
      (node (ref "ARDUINO_MOTORS") (pin "19") (pinfunction "DIG13_PB5_19") (pintype "bidirectional"))
    )
    (net (code "72") (name "unconnected-(ARDUINO_MOTORS-PC2_ADC2-Pad25)") (class "Default")
      (node (ref "ARDUINO_MOTORS") (pin "25") (pinfunction "PC2_ADC2_25") (pintype "bidirectional"))
    )
    (net (code "73") (name "unconnected-(ARDUINO_MOTORS-PC3_ADC3-Pad26)") (class "Default")
      (node (ref "ARDUINO_MOTORS") (pin "26") (pinfunction "PC3_ADC3_26") (pintype "bidirectional"))
    )
    (net (code "74") (name "unconnected-(ARDUINO_MOTORS-PC4_ADC4-Pad27)") (class "Default")
      (node (ref "ARDUINO_MOTORS") (pin "27") (pinfunction "PC4_ADC4_27") (pintype "bidirectional"))
    )
    (net (code "75") (name "unconnected-(ARDUINO_MOTORS-PC5_ADC5-Pad28)") (class "Default")
      (node (ref "ARDUINO_MOTORS") (pin "28") (pinfunction "PC5_ADC5_28") (pintype "bidirectional"))
    )
    (net (code "76") (name "unconnected-(ARDUINO_SENSORS-AREF-Pad21)") (class "Default")
      (node (ref "ARDUINO_SENSORS") (pin "21") (pinfunction "AREF_21") (pintype "passive"))
    )
    (net (code "77") (name "unconnected-(ARDUINO_SENSORS-DIG12_PB4-Pad18)") (class "Default")
      (node (ref "ARDUINO_SENSORS") (pin "18") (pinfunction "DIG12_PB4_18") (pintype "bidirectional"))
    )
    (net (code "78") (name "unconnected-(ARDUINO_SENSORS-DIG13_PB5-Pad19)") (class "Default")
      (node (ref "ARDUINO_SENSORS") (pin "19") (pinfunction "DIG13_PB5_19") (pintype "bidirectional"))
    )
    (net (code "79") (name "unconnected-(ARDUINO_SENSORS-PC0_ADC0-Pad23)") (class "Default")
      (node (ref "ARDUINO_SENSORS") (pin "23") (pinfunction "PC0_ADC0_23") (pintype "bidirectional"))
    )
    (net (code "80") (name "unconnected-(ARDUINO_SENSORS-PC1_ADC1-Pad24)") (class "Default")
      (node (ref "ARDUINO_SENSORS") (pin "24") (pinfunction "PC1_ADC1_24") (pintype "bidirectional"))
    )
    (net (code "81") (name "unconnected-(ARDUINO_SENSORS-PC2_ADC2-Pad25)") (class "Default")
      (node (ref "ARDUINO_SENSORS") (pin "25") (pinfunction "PC2_ADC2_25") (pintype "bidirectional"))
    )
    (net (code "82") (name "unconnected-(ARDUINO_SENSORS-PC3_ADC3-Pad26)") (class "Default")
      (node (ref "ARDUINO_SENSORS") (pin "26") (pinfunction "PC3_ADC3_26") (pintype "bidirectional"))
    )
    (net (code "83") (name "unconnected-(ARDUINO_SENSORS-PC4_ADC4-Pad27)") (class "Default")
      (node (ref "ARDUINO_SENSORS") (pin "27") (pinfunction "PC4_ADC4_27") (pintype "bidirectional"))
    )
    (net (code "84") (name "unconnected-(ARDUINO_SENSORS-PC5_ADC5-Pad28)") (class "Default")
      (node (ref "ARDUINO_SENSORS") (pin "28") (pinfunction "PC5_ADC5_28") (pintype "bidirectional"))
    )
    (net (code "85") (name "unconnected-(J1-Pad1)") (class "Default")
      (node (ref "J1") (pin "1") (pinfunction "1_1") (pintype "bidirectional"))
    )
    (net (code "86") (name "unconnected-(J1-Pad2)") (class "Default")
      (node (ref "J1") (pin "2") (pinfunction "2_2") (pintype "bidirectional"))
    )
    (net (code "87") (name "unconnected-(J1-Pad3)") (class "Default")
      (node (ref "J1") (pin "3") (pinfunction "3_3") (pintype "bidirectional"))
    )
    (net (code "88") (name "unconnected-(J1-Pad4)") (class "Default")
      (node (ref "J1") (pin "4") (pinfunction "4_4") (pintype "bidirectional"))
    )
    (net (code "89") (name "unconnected-(J1-Pad5)") (class "Default")
      (node (ref "J1") (pin "5") (pinfunction "5_5") (pintype "bidirectional"))
    )
    (net (code "90") (name "unconnected-(J1-Pad6)") (class "Default")
      (node (ref "J1") (pin "6") (pinfunction "6_6") (pintype "bidirectional"))
    )
    (net (code "91") (name "unconnected-(J1-Pad7)") (class "Default")
      (node (ref "J1") (pin "7") (pinfunction "7_7") (pintype "bidirectional"))
    )
    (net (code "92") (name "unconnected-(J1-Pad8)") (class "Default")
      (node (ref "J1") (pin "8") (pinfunction "8_8") (pintype "bidirectional"))
    )
    (net (code "93") (name "unconnected-(U1-DB0-Pad7)") (class "Default")
      (node (ref "U1") (pin "7") (pinfunction "DB0_7") (pintype "unspecified"))
    )
    (net (code "94") (name "unconnected-(U1-DB1-Pad8)") (class "Default")
      (node (ref "U1") (pin "8") (pinfunction "DB1_8") (pintype "unspecified"))
    )
    (net (code "95") (name "unconnected-(U1-DB2-Pad9)") (class "Default")
      (node (ref "U1") (pin "9") (pinfunction "DB2_9") (pintype "unspecified"))
    )
    (net (code "96") (name "unconnected-(U1-DB3-Pad10)") (class "Default")
      (node (ref "U1") (pin "10") (pinfunction "DB3_10") (pintype "unspecified"))
    )
    (net (code "97") (name "unconnected-(U2-(PWM)GPIO4{slash}D2-Pad28)") (class "Default")
      (node (ref "U2") (pin "28") (pinfunction "(PWM)GPIO4/D2_28") (pintype "unspecified"))
    )
    (net (code "98") (name "unconnected-(U2-(PWM)GPIO12{slash}D6-Pad22)") (class "Default")
      (node (ref "U2") (pin "22") (pinfunction "(PWM)GPIO12/D6_22") (pintype "unspecified"))
    )
    (net (code "99") (name "unconnected-(U2-(PWM)GPIO14{slash}D5-Pad23)") (class "Default")
      (node (ref "U2") (pin "23") (pinfunction "(PWM)GPIO14/D5_23") (pintype "unspecified"))
    )
    (net (code "100") (name "unconnected-(U2-(PWM)GPIO15{slash}D8-Pad20)") (class "Default")
      (node (ref "U2") (pin "20") (pinfunction "(PWM)GPIO15/D8_20") (pintype "unspecified"))
    )
    (net (code "101") (name "unconnected-(U2-3.3V-Pad16)") (class "Default")
      (node (ref "U2") (pin "16") (pinfunction "3.3V_16") (pintype "unspecified"))
    )
    (net (code "102") (name "unconnected-(U2-3.3V-Pad25)") (class "Default")
      (node (ref "U2") (pin "25") (pinfunction "3.3V_25") (pintype "unspecified"))
    )
    (net (code "103") (name "unconnected-(U2-A0-Pad1)") (class "Default")
      (node (ref "U2") (pin "1") (pinfunction "A0_1") (pintype "unspecified"))
    )
    (net (code "104") (name "unconnected-(U2-EN-Pad12)") (class "Default")
      (node (ref "U2") (pin "12") (pinfunction "EN_12") (pintype "unspecified"))
    )
    (net (code "105") (name "unconnected-(U2-GND-Pad10)") (class "Default")
      (node (ref "U2") (pin "10") (pinfunction "GND_10") (pintype "unspecified"))
    )
    (net (code "106") (name "unconnected-(U2-GND-Pad14)") (class "Default")
      (node (ref "U2") (pin "14") (pinfunction "GND_14") (pintype "unspecified"))
    )
    (net (code "107") (name "unconnected-(U2-GND-Pad17)") (class "Default")
      (node (ref "U2") (pin "17") (pinfunction "GND_17") (pintype "unspecified"))
    )
    (net (code "108") (name "unconnected-(U2-GND-Pad24)") (class "Default")
      (node (ref "U2") (pin "24") (pinfunction "GND_24") (pintype "unspecified"))
    )
    (net (code "109") (name "unconnected-(U2-GPIO0{slash}D3-Pad27)") (class "Default")
      (node (ref "U2") (pin "27") (pinfunction "GPIO0/D3_27") (pintype "unspecified"))
    )
    (net (code "110") (name "unconnected-(U2-GPIO1{slash}TX-Pad18)") (class "Default")
      (node (ref "U2") (pin "18") (pinfunction "GPIO1/TX_18") (pintype "unspecified"))
    )
    (net (code "111") (name "unconnected-(U2-GPIO3{slash}RX-Pad19)") (class "Default")
      (node (ref "U2") (pin "19") (pinfunction "GPIO3/RX_19") (pintype "unspecified"))
    )
    (net (code "112") (name "unconnected-(U2-GPIO5{slash}D1-Pad29)") (class "Default")
      (node (ref "U2") (pin "29") (pinfunction "GPIO5/D1_29") (pintype "unspecified"))
    )
    (net (code "113") (name "unconnected-(U2-GPIO13{slash}D7-Pad21)") (class "Default")
      (node (ref "U2") (pin "21") (pinfunction "GPIO13/D7_21") (pintype "unspecified"))
    )
    (net (code "114") (name "unconnected-(U2-GPIO16{slash}D0-Pad30)") (class "Default")
      (node (ref "U2") (pin "30") (pinfunction "GPIO16/D0_30") (pintype "unspecified"))
    )
    (net (code "115") (name "unconnected-(U2-RST-Pad13)") (class "Default")
      (node (ref "U2") (pin "13") (pinfunction "RST_13") (pintype "unspecified"))
    )
    (net (code "116") (name "unconnected-(U2-S0{slash}GPIO7-Pad8)") (class "Default")
      (node (ref "U2") (pin "8") (pinfunction "S0/GPIO7_8") (pintype "unspecified"))
    )
    (net (code "117") (name "unconnected-(U2-S1{slash}GPIO8-Pad6)") (class "Default")
      (node (ref "U2") (pin "6") (pinfunction "S1/GPIO8_6") (pintype "unspecified"))
    )
    (net (code "118") (name "unconnected-(U2-S2{slash}GPIO9-Pad5)") (class "Default")
      (node (ref "U2") (pin "5") (pinfunction "S2/GPIO9_5") (pintype "unspecified"))
    )
    (net (code "119") (name "unconnected-(U2-S3{slash}GPIO10-Pad4)") (class "Default")
      (node (ref "U2") (pin "4") (pinfunction "S3/GPIO10_4") (pintype "unspecified"))
    )
    (net (code "120") (name "unconnected-(U2-SC{slash}GPIO11-Pad7)") (class "Default")
      (node (ref "U2") (pin "7") (pinfunction "SC/GPIO11_7") (pintype "unspecified"))
    )
    (net (code "121") (name "unconnected-(U2-SK{slash}GPIO6-Pad9)") (class "Default")
      (node (ref "U2") (pin "9") (pinfunction "SK/GPIO6_9") (pintype "unspecified"))
    )
    (net (code "122") (name "unconnected-(U2-VU-Pad3)") (class "Default")
      (node (ref "U2") (pin "3") (pinfunction "VU_3") (pintype "unspecified"))
    )
    (net (code "123") (name "unconnected-(U2-Vin-Pad15)") (class "Default")
      (node (ref "U2") (pin "15") (pinfunction "Vin_15") (pintype "unspecified"))
    )
  )
)
